# Phototransistor2.net
KiCad netlist of a schematic drawn in EAGLE
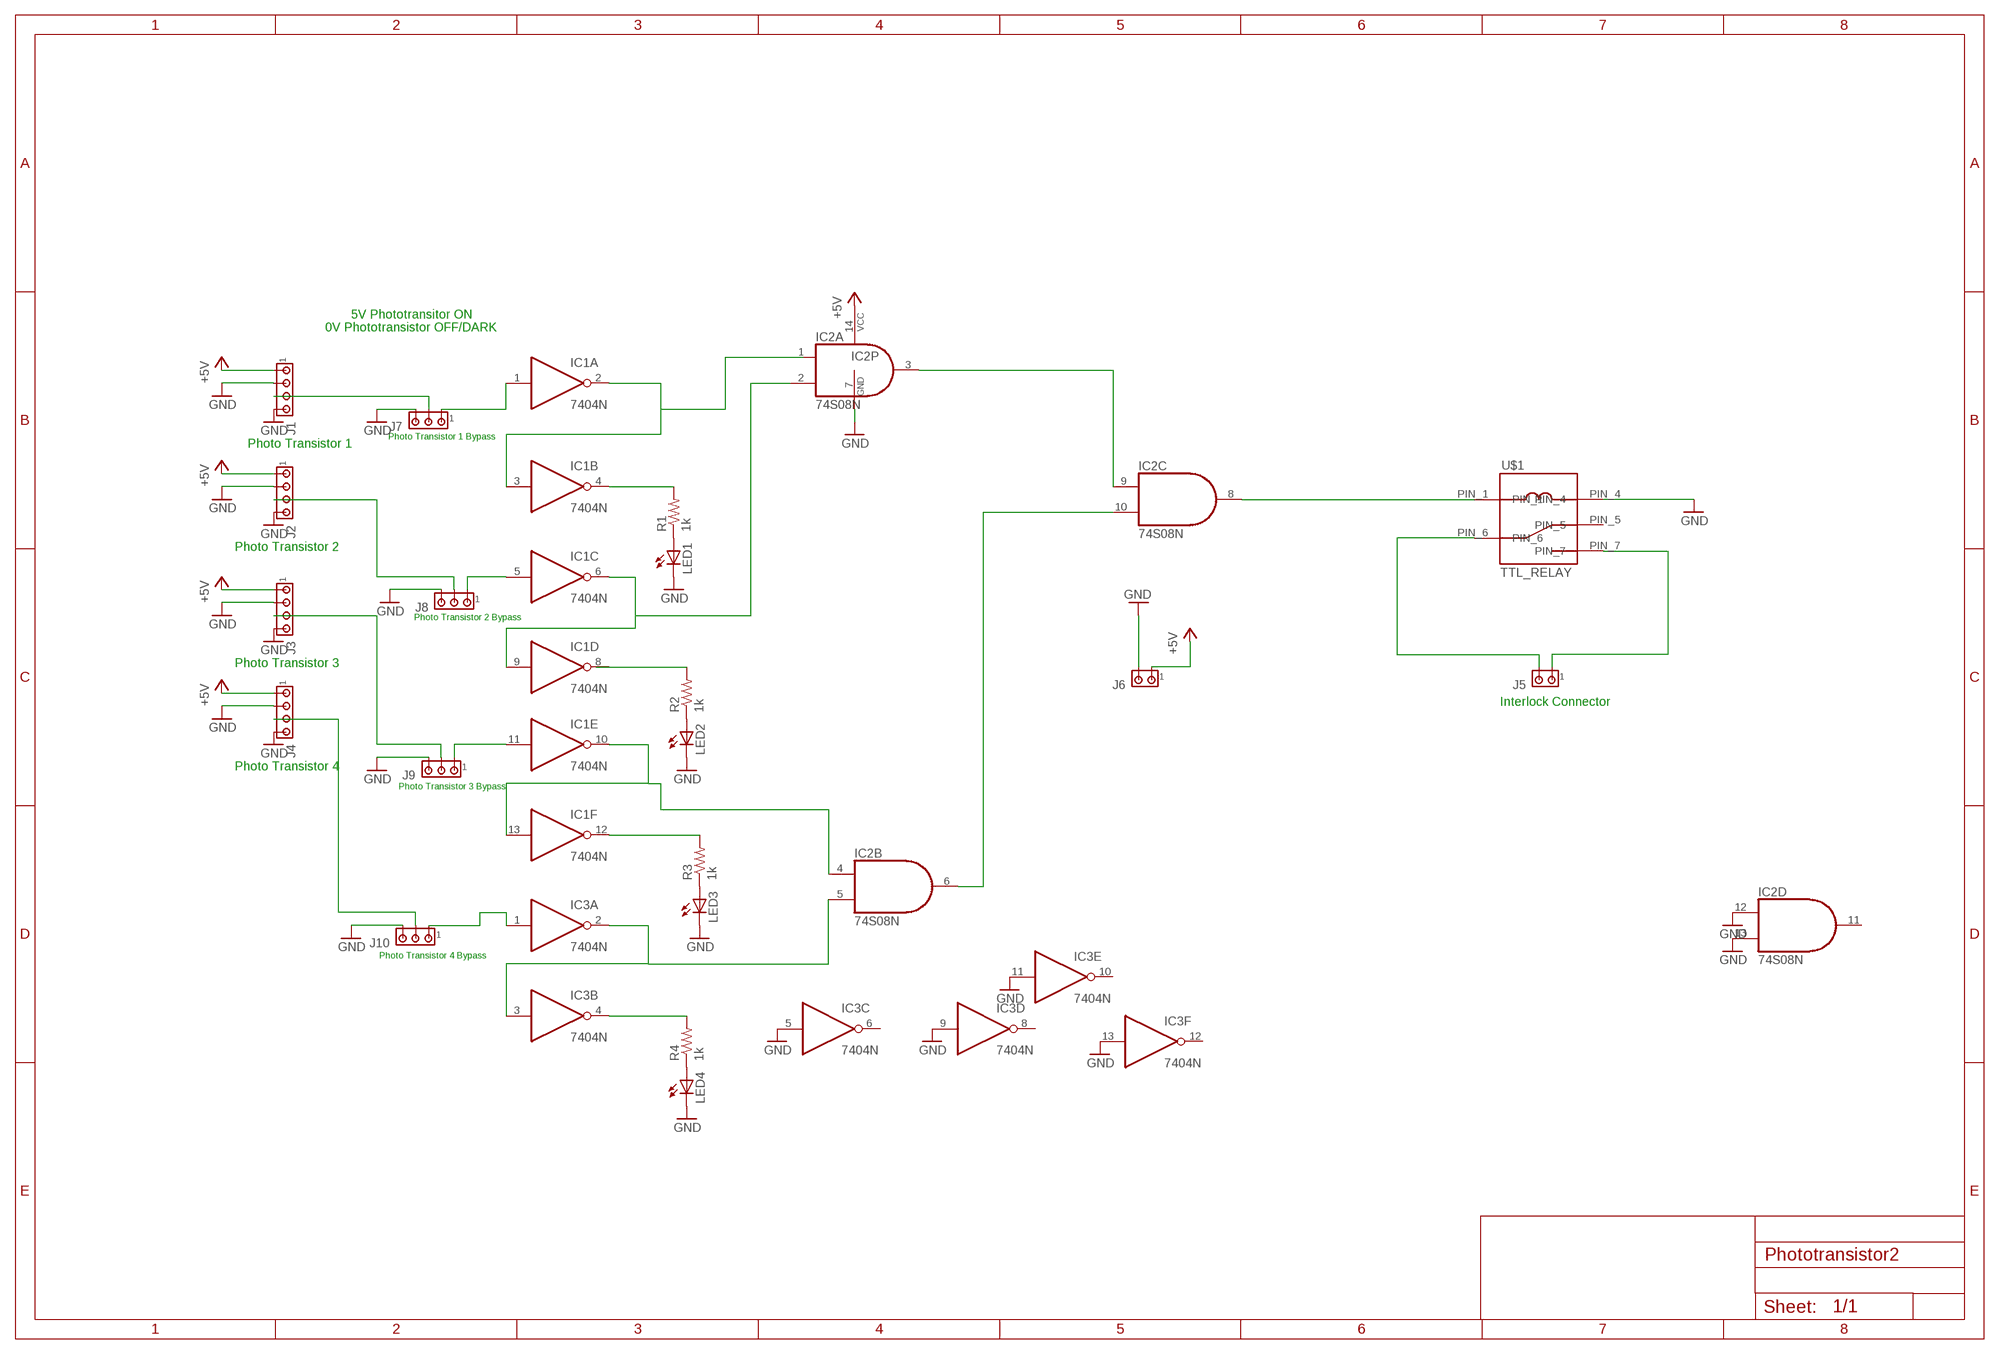
[diagram p0: schematic, sheet 1]

(export (version "E")
  (design (tool "Eeschema 10.0.6"))
  (components
    (comp (ref "IC1")
      (value "7404N")
      (footprint "eagle-import:DIL14")
      (libsource (lib "eagle-import") (part "7404N"))
    )
    (comp (ref "IC2")
      (value "74S08N")
      (footprint "eagle-import:DIL14")
      (libsource (lib "eagle-import") (part "7408NS"))
    )
    (comp (ref "IC3")
      (value "7404N")
      (footprint "eagle-import:DIL14")
      (libsource (lib "eagle-import") (part "7404N"))
    )
    (comp (ref "J1")
      (value "MTA04-100")
      (footprint "eagle-import:10X04MTA")
      (libsource (lib "eagle-import") (part "MTA04-100"))
    )
    (comp (ref "J2")
      (value "MTA04-100")
      (footprint "eagle-import:10X04MTA")
      (libsource (lib "eagle-import") (part "MTA04-100"))
    )
    (comp (ref "J3")
      (value "MTA04-100")
      (footprint "eagle-import:10X04MTA")
      (libsource (lib "eagle-import") (part "MTA04-100"))
    )
    (comp (ref "J4")
      (value "MTA04-100")
      (footprint "eagle-import:10X04MTA")
      (libsource (lib "eagle-import") (part "MTA04-100"))
    )
    (comp (ref "J5")
      (value "MTA02-100")
      (footprint "eagle-import:10X02MTA")
      (libsource (lib "eagle-import") (part "MTA02-100"))
    )
    (comp (ref "J6")
      (value "MTA02-100")
      (footprint "eagle-import:10X02MTA")
      (libsource (lib "eagle-import") (part "MTA02-100"))
    )
    (comp (ref "J7")
      (value "MTA03-100")
      (footprint "eagle-import:10X03MTA")
      (libsource (lib "eagle-import") (part "MTA03-100"))
    )
    (comp (ref "J8")
      (value "MTA03-100")
      (footprint "eagle-import:10X03MTA")
      (libsource (lib "eagle-import") (part "MTA03-100"))
    )
    (comp (ref "J9")
      (value "MTA03-100")
      (footprint "eagle-import:10X03MTA")
      (libsource (lib "eagle-import") (part "MTA03-100"))
    )
    (comp (ref "J10")
      (value "MTA03-100")
      (footprint "eagle-import:10X03MTA")
      (libsource (lib "eagle-import") (part "MTA03-100"))
    )
    (comp (ref "LED1")
      (value "LED3MM")
      (footprint "eagle-import:LED3MM")
      (libsource (lib "eagle-import") (part "LED3MM"))
    )
    (comp (ref "LED2")
      (value "LED3MM")
      (footprint "eagle-import:LED3MM")
      (libsource (lib "eagle-import") (part "LED3MM"))
    )
    (comp (ref "LED3")
      (value "LED3MM")
      (footprint "eagle-import:LED3MM")
      (libsource (lib "eagle-import") (part "LED3MM"))
    )
    (comp (ref "LED4")
      (value "LED3MM")
      (footprint "eagle-import:LED3MM")
      (libsource (lib "eagle-import") (part "LED3MM"))
    )
    (comp (ref "R1")
      (value "1k")
      (footprint "eagle-import:0204_7")
      (libsource (lib "eagle-import") (part "R-US_0204/7"))
    )
    (comp (ref "R2")
      (value "1k")
      (footprint "eagle-import:0204_7")
      (libsource (lib "eagle-import") (part "R-US_0204/7"))
    )
    (comp (ref "R3")
      (value "1k")
      (footprint "eagle-import:0204_7")
      (libsource (lib "eagle-import") (part "R-US_0204/7"))
    )
    (comp (ref "R4")
      (value "1k")
      (footprint "eagle-import:0204_7")
      (libsource (lib "eagle-import") (part "R-US_0204/7"))
    )
    (comp (ref "U$1")
      (value "TTL_RELAY")
      (footprint "eagle-import:R1OS-E1Y1-J1.0K")
      (libsource (lib "eagle-import") (part "TTL_RELAY"))
    )
  )
  (nets
    (net (code "1") (name "+5V") (class "Default")
      (node (ref "IC2") (pin "14") (pinfunction "VCC_14") (pintype "power_in"))
      (node (ref "J1") (pin "1") (pinfunction "1_1") (pintype "passive"))
      (node (ref "J2") (pin "1") (pinfunction "1_1") (pintype "passive"))
      (node (ref "J3") (pin "1") (pinfunction "1_1") (pintype "passive"))
      (node (ref "J4") (pin "1") (pinfunction "1_1") (pintype "passive"))
      (node (ref "J6") (pin "1") (pinfunction "1_1") (pintype "passive"))
    )
    (net (code "2") (name "GND") (class "Default")
      (node (ref "IC2") (pin "12") (pinfunction "I0_12") (pintype "input"))
      (node (ref "IC2") (pin "13") (pinfunction "I1_13") (pintype "input"))
      (node (ref "IC2") (pin "7") (pinfunction "GND_7") (pintype "power_in"))
      (node (ref "IC3") (pin "11") (pinfunction "I_11") (pintype "input"))
      (node (ref "IC3") (pin "13") (pinfunction "I_13") (pintype "input"))
      (node (ref "IC3") (pin "5") (pinfunction "I_5") (pintype "input"))
      (node (ref "IC3") (pin "9") (pinfunction "I_9") (pintype "input"))
      (node (ref "J1") (pin "2") (pinfunction "2_2") (pintype "passive"))
      (node (ref "J1") (pin "4") (pinfunction "4_4") (pintype "passive"))
      (node (ref "J10") (pin "3") (pinfunction "3_3") (pintype "passive"))
      (node (ref "J2") (pin "2") (pinfunction "2_2") (pintype "passive"))
      (node (ref "J2") (pin "4") (pinfunction "4_4") (pintype "passive"))
      (node (ref "J3") (pin "2") (pinfunction "2_2") (pintype "passive"))
      (node (ref "J3") (pin "4") (pinfunction "4_4") (pintype "passive"))
      (node (ref "J4") (pin "2") (pinfunction "2_2") (pintype "passive"))
      (node (ref "J4") (pin "4") (pinfunction "4_4") (pintype "passive"))
      (node (ref "J6") (pin "2") (pinfunction "2_2") (pintype "passive"))
      (node (ref "J7") (pin "3") (pinfunction "3_3") (pintype "passive"))
      (node (ref "J8") (pin "3") (pinfunction "3_3") (pintype "passive"))
      (node (ref "J9") (pin "3") (pinfunction "3_3") (pintype "passive"))
      (node (ref "LED1") (pin "K") (pinfunction "C_K") (pintype "passive"))
      (node (ref "LED2") (pin "K") (pinfunction "C_K") (pintype "passive"))
      (node (ref "LED3") (pin "K") (pinfunction "C_K") (pintype "passive"))
      (node (ref "LED4") (pin "K") (pinfunction "C_K") (pintype "passive"))
      (node (ref "U$1") (pin "PIN_4") (pinfunction "PIN_4_PIN_4") (pintype "bidirectional"))
    )
    (net (code "3") (name "Net-(IC1A-I)") (class "Default")
      (node (ref "IC1") (pin "1") (pinfunction "I_1") (pintype "input"))
      (node (ref "J7") (pin "1") (pinfunction "1_1") (pintype "passive"))
    )
    (net (code "4") (name "Net-(IC1A-O)") (class "Default")
      (node (ref "IC1") (pin "2") (pinfunction "O_2") (pintype "output"))
      (node (ref "IC1") (pin "3") (pinfunction "I_3") (pintype "input"))
    )
    (net (code "5") (name "Net-(IC1B-O)") (class "Default")
      (node (ref "IC1") (pin "4") (pinfunction "O_4") (pintype "output"))
      (node (ref "R1") (pin "2") (pinfunction "2_2") (pintype "passive"))
    )
    (net (code "6") (name "Net-(IC1C-I)") (class "Default")
      (node (ref "IC1") (pin "5") (pinfunction "I_5") (pintype "input"))
      (node (ref "J8") (pin "1") (pinfunction "1_1") (pintype "passive"))
    )
    (net (code "7") (name "Net-(IC1C-O)") (class "Default")
      (node (ref "IC1") (pin "6") (pinfunction "O_6") (pintype "output"))
      (node (ref "IC1") (pin "9") (pinfunction "I_9") (pintype "input"))
      (node (ref "IC2") (pin "2") (pinfunction "I1_2") (pintype "input"))
    )
    (net (code "8") (name "Net-(IC1E-I)") (class "Default")
      (node (ref "IC1") (pin "11") (pinfunction "I_11") (pintype "input"))
      (node (ref "J9") (pin "1") (pinfunction "1_1") (pintype "passive"))
    )
    (net (code "9") (name "Net-(IC1E-O)") (class "Default")
      (node (ref "IC1") (pin "10") (pinfunction "O_10") (pintype "output"))
      (node (ref "IC1") (pin "13") (pinfunction "I_13") (pintype "input"))
      (node (ref "IC2") (pin "4") (pinfunction "I0_4") (pintype "input"))
    )
    (net (code "10") (name "Net-(IC1F-O)") (class "Default")
      (node (ref "IC1") (pin "12") (pinfunction "O_12") (pintype "output"))
      (node (ref "R3") (pin "2") (pinfunction "2_2") (pintype "passive"))
    )
    (net (code "11") (name "Net-(IC2A-O)") (class "Default")
      (node (ref "IC2") (pin "3") (pinfunction "O_3") (pintype "output"))
      (node (ref "IC2") (pin "9") (pinfunction "I0_9") (pintype "input"))
    )
    (net (code "12") (name "Net-(IC2B-I1)") (class "Default")
      (node (ref "IC2") (pin "5") (pinfunction "I1_5") (pintype "input"))
      (node (ref "IC3") (pin "2") (pinfunction "O_2") (pintype "output"))
      (node (ref "IC3") (pin "3") (pinfunction "I_3") (pintype "input"))
    )
    (net (code "13") (name "Net-(IC2B-O)") (class "Default")
      (node (ref "IC2") (pin "10") (pinfunction "I1_10") (pintype "input"))
      (node (ref "IC2") (pin "6") (pinfunction "O_6") (pintype "output"))
    )
    (net (code "14") (name "Net-(IC2C-O)") (class "Default")
      (node (ref "IC2") (pin "8") (pinfunction "O_8") (pintype "output"))
      (node (ref "U$1") (pin "PIN_1") (pinfunction "PIN_1_PIN_1") (pintype "bidirectional"))
    )
    (net (code "15") (name "Net-(IC3A-I)") (class "Default")
      (node (ref "IC3") (pin "1") (pinfunction "I_1") (pintype "input"))
      (node (ref "J10") (pin "1") (pinfunction "1_1") (pintype "passive"))
    )
    (net (code "16") (name "Net-(IC3B-O)") (class "Default")
      (node (ref "IC3") (pin "4") (pinfunction "O_4") (pintype "output"))
      (node (ref "R4") (pin "2") (pinfunction "2_2") (pintype "passive"))
    )
    (net (code "17") (name "Net-(J1-Pad3)") (class "Default")
      (node (ref "J1") (pin "3") (pinfunction "3_3") (pintype "passive"))
      (node (ref "J7") (pin "2") (pinfunction "2_2") (pintype "passive"))
    )
    (net (code "18") (name "Net-(J2-Pad3)") (class "Default")
      (node (ref "J2") (pin "3") (pinfunction "3_3") (pintype "passive"))
      (node (ref "J8") (pin "2") (pinfunction "2_2") (pintype "passive"))
    )
    (net (code "19") (name "Net-(J3-Pad3)") (class "Default")
      (node (ref "J3") (pin "3") (pinfunction "3_3") (pintype "passive"))
      (node (ref "J9") (pin "2") (pinfunction "2_2") (pintype "passive"))
    )
    (net (code "20") (name "Net-(J5-Pad1)") (class "Default")
      (node (ref "J5") (pin "1") (pinfunction "1_1") (pintype "passive"))
      (node (ref "U$1") (pin "PIN_7") (pinfunction "PIN_7_PIN_7") (pintype "bidirectional"))
    )
    (net (code "21") (name "Net-(J5-Pad2)") (class "Default")
      (node (ref "J5") (pin "2") (pinfunction "2_2") (pintype "passive"))
      (node (ref "U$1") (pin "PIN_6") (pinfunction "PIN_6_PIN_6") (pintype "bidirectional"))
    )
    (net (code "22") (name "Net-(J10-Pad2)") (class "Default")
      (node (ref "J10") (pin "2") (pinfunction "2_2") (pintype "passive"))
      (node (ref "J4") (pin "3") (pinfunction "3_3") (pintype "passive"))
    )
    (net (code "23") (name "Net-(LED1-PadA)") (class "Default")
      (node (ref "LED1") (pin "A") (pinfunction "A_A") (pintype "passive"))
      (node (ref "R1") (pin "1") (pinfunction "1_1") (pintype "passive"))
    )
    (net (code "24") (name "Net-(LED2-PadA)") (class "Default")
      (node (ref "LED2") (pin "A") (pinfunction "A_A") (pintype "passive"))
      (node (ref "R2") (pin "1") (pinfunction "1_1") (pintype "passive"))
    )
    (net (code "25") (name "Net-(LED3-PadA)") (class "Default")
      (node (ref "LED3") (pin "A") (pinfunction "A_A") (pintype "passive"))
      (node (ref "R3") (pin "1") (pinfunction "1_1") (pintype "passive"))
    )
    (net (code "26") (name "Net-(LED4-PadA)") (class "Default")
      (node (ref "LED4") (pin "A") (pinfunction "A_A") (pintype "passive"))
      (node (ref "R4") (pin "1") (pinfunction "1_1") (pintype "passive"))
    )
    (net (code "27") (name "unconnected-(IC1D-O-Pad8)") (class "Default")
      (node (ref "IC1") (pin "8") (pinfunction "O_8") (pintype "output"))
    )
    (net (code "28") (name "unconnected-(IC2A-I0-Pad1)") (class "Default")
      (node (ref "IC2") (pin "1") (pinfunction "I0_1") (pintype "input"))
    )
    (net (code "29") (name "unconnected-(IC2D-O-Pad11)") (class "Default")
      (node (ref "IC2") (pin "11") (pinfunction "O_11") (pintype "output"))
    )
    (net (code "30") (name "unconnected-(IC3C-O-Pad6)") (class "Default")
      (node (ref "IC3") (pin "6") (pinfunction "O_6") (pintype "output"))
    )
    (net (code "31") (name "unconnected-(IC3D-O-Pad8)") (class "Default")
      (node (ref "IC3") (pin "8") (pinfunction "O_8") (pintype "output"))
    )
    (net (code "32") (name "unconnected-(IC3E-O-Pad10)") (class "Default")
      (node (ref "IC3") (pin "10") (pinfunction "O_10") (pintype "output"))
    )
    (net (code "33") (name "unconnected-(IC3F-O-Pad12)") (class "Default")
      (node (ref "IC3") (pin "12") (pinfunction "O_12") (pintype "output"))
    )
    (net (code "34") (name "unconnected-(R2-Pad2)") (class "Default")
      (node (ref "R2") (pin "2") (pinfunction "2_2") (pintype "passive"))
    )
    (net (code "35") (name "unconnected-(U$1-PadPIN_5)") (class "Default")
      (node (ref "U$1") (pin "PIN_5") (pinfunction "PIN_5_PIN_5") (pintype "bidirectional"))
    )
  )
)
